# PSPS_AVNC_SRD_central-2020-11-2_FABRICAT.net
KiCad netlist of a schematic drawn in EAGLE
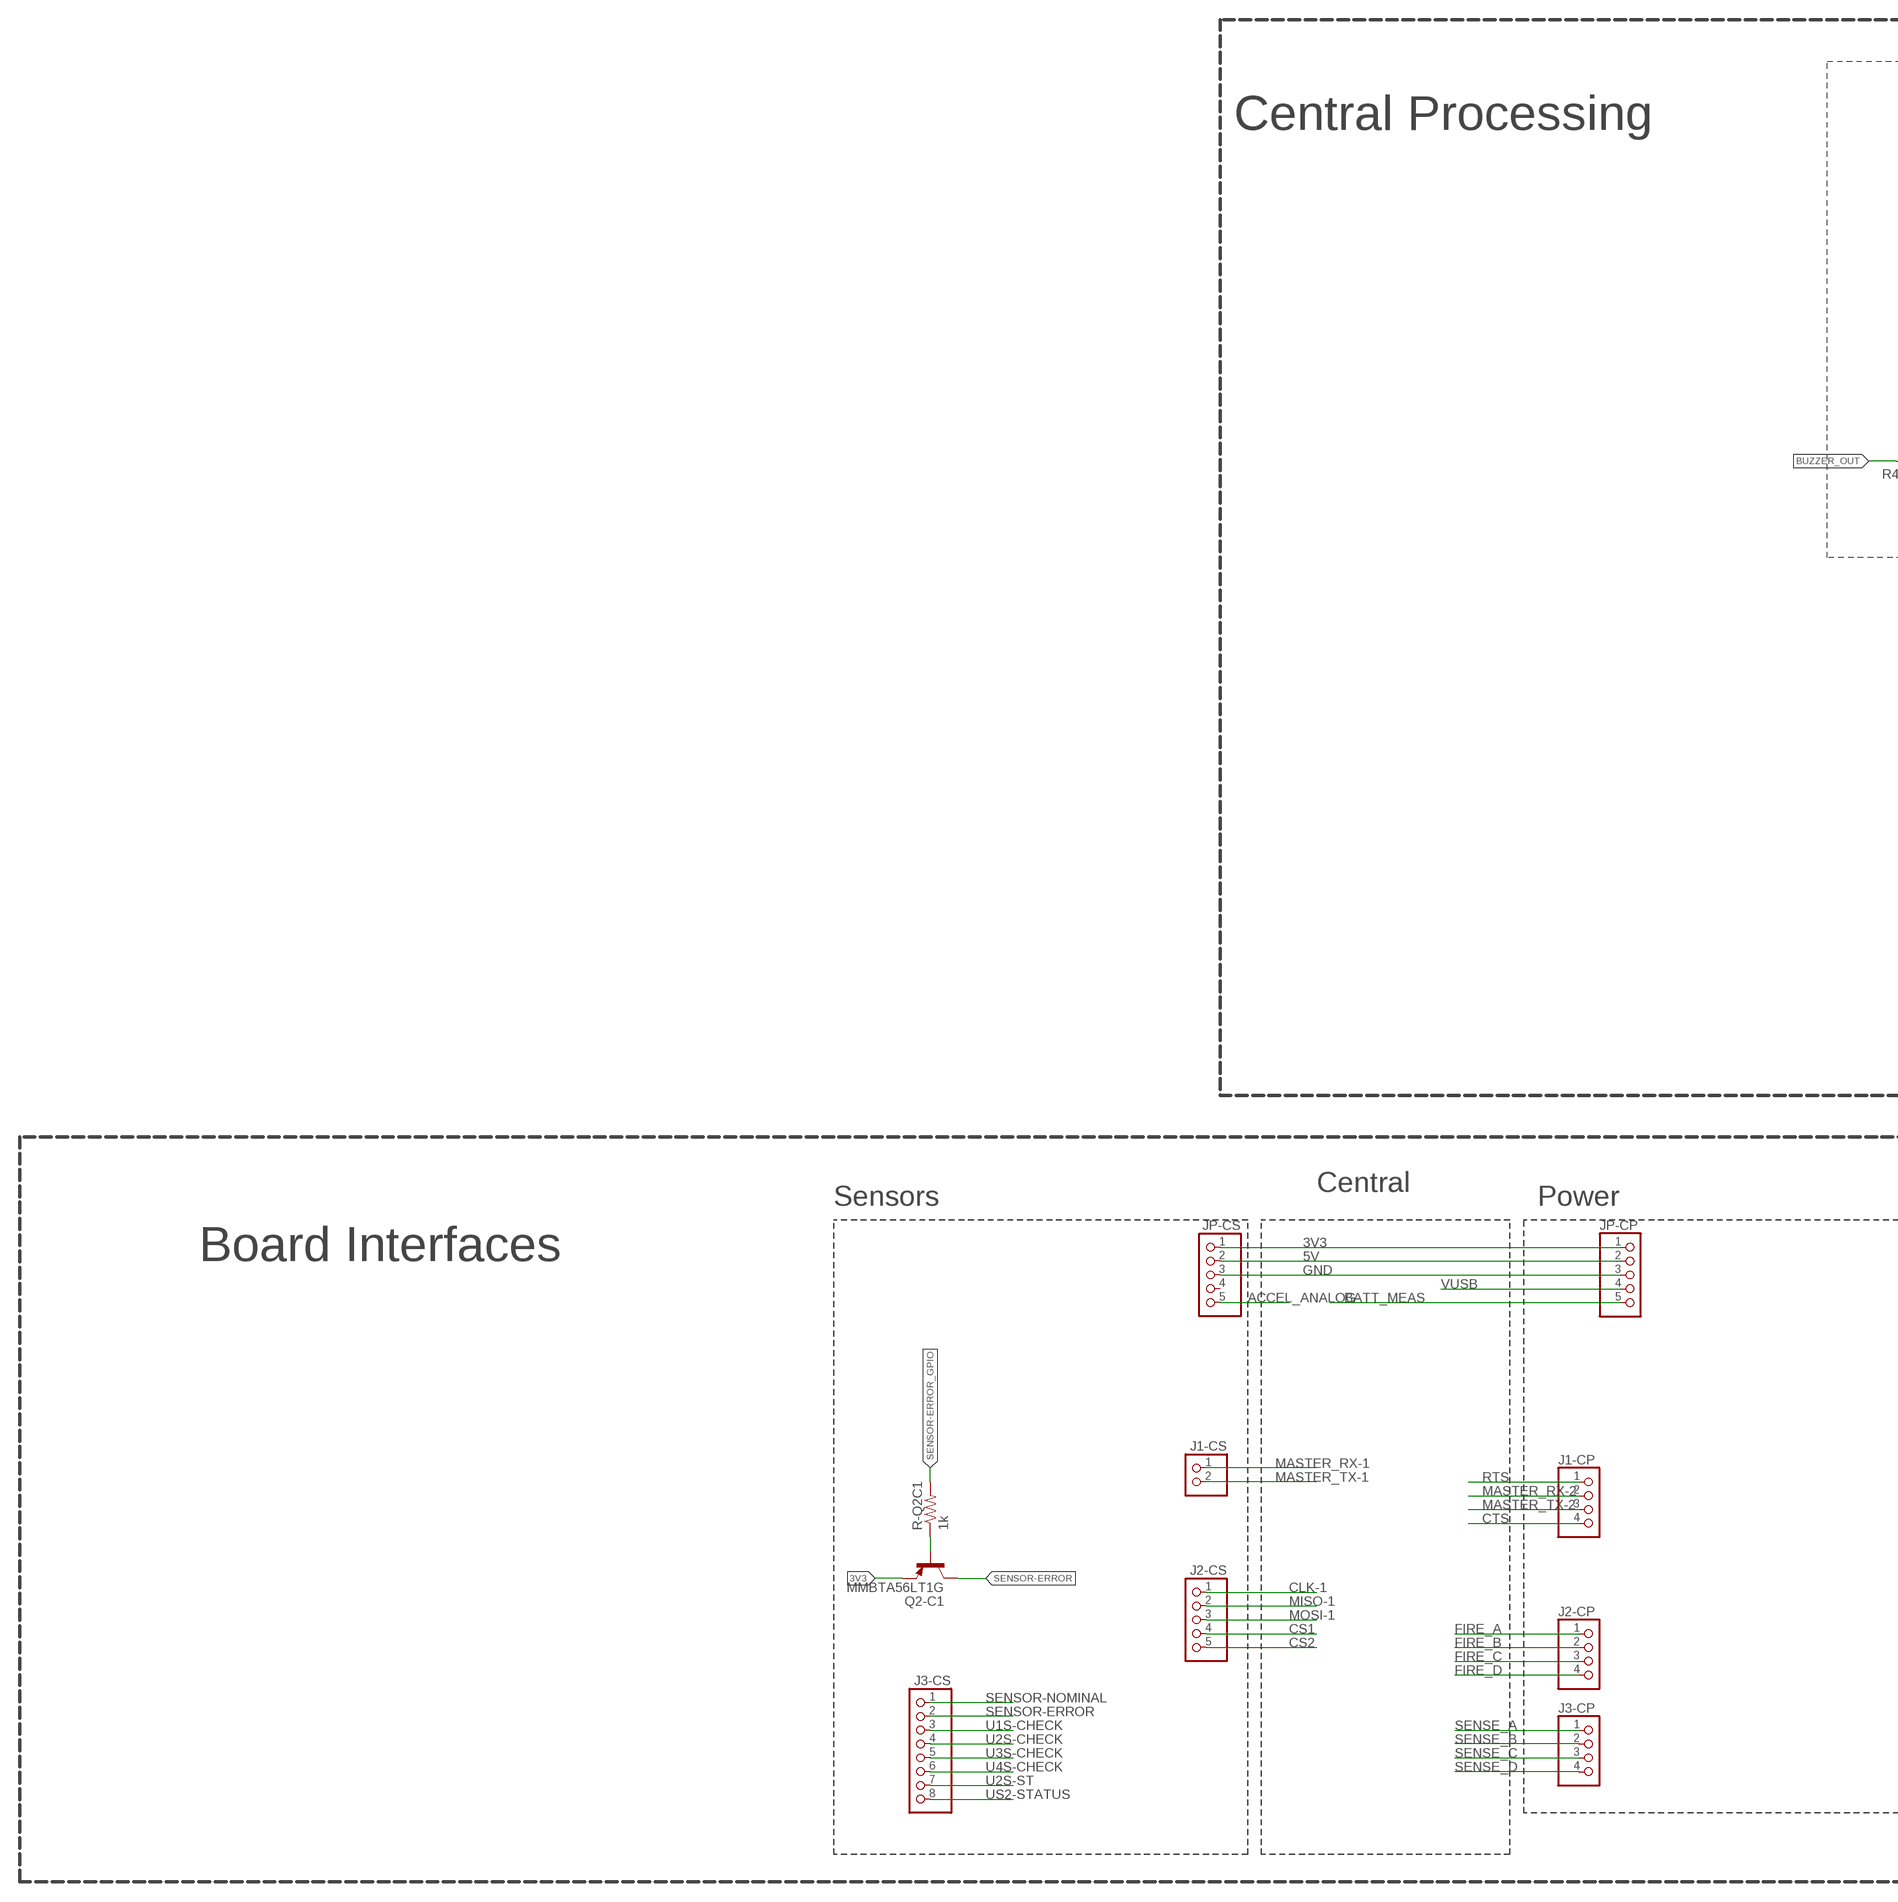
[diagram p0: schematic, sheet 1, part 1 of 2]
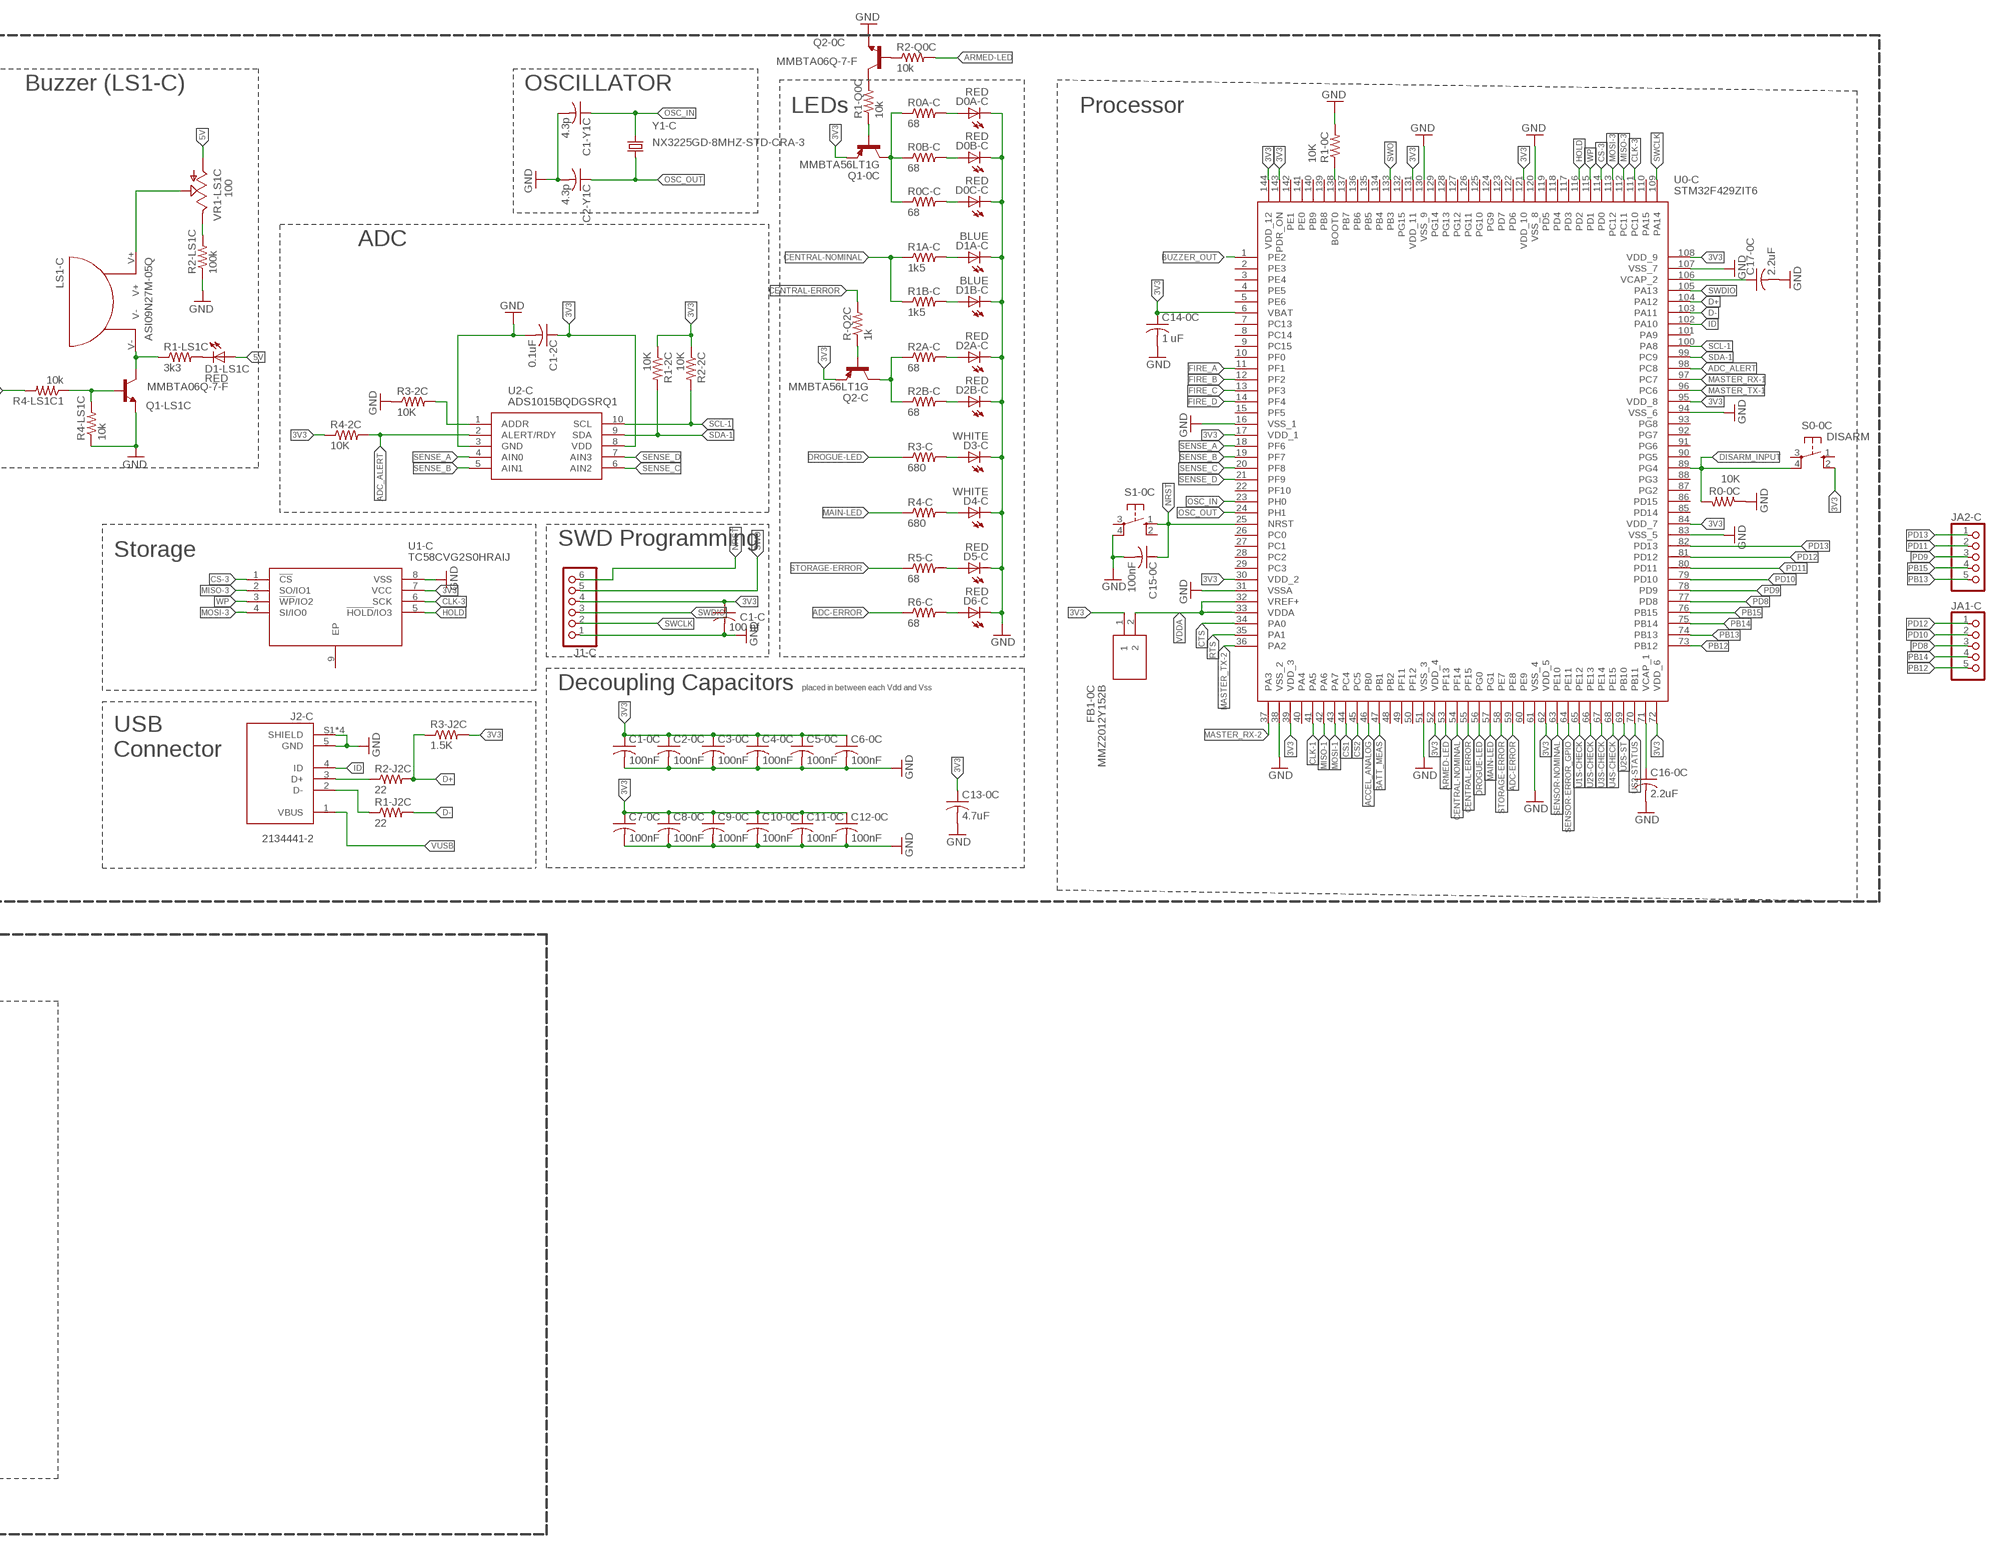
[diagram p1: schematic, sheet 1, part 2 of 2]

(export (version "E")
  (design (tool "Eeschema 10.0.6"))
  (components
    (comp (ref "C1-0C")
      (value "100nF")
      (footprint "eagle-import:C0805")
      (libsource (lib "eagle-import") (part "C-USC0805"))
    )
    (comp (ref "C1-2C")
      (value "0.1uF")
      (footprint "eagle-import:C0805")
      (libsource (lib "eagle-import") (part "C-USC0805"))
    )
    (comp (ref "C1-C")
      (value "100 nf")
      (footprint "eagle-import:C0805")
      (libsource (lib "eagle-import") (part "C-USC0805"))
    )
    (comp (ref "C1-Y1C")
      (value "4.3p")
      (footprint "eagle-import:C0805")
      (libsource (lib "eagle-import") (part "C-USC0805"))
    )
    (comp (ref "C2-0C")
      (value "100nF")
      (footprint "eagle-import:C0805")
      (libsource (lib "eagle-import") (part "C-USC0805"))
    )
    (comp (ref "C2-Y1C")
      (value "4.3p")
      (footprint "eagle-import:C0805")
      (libsource (lib "eagle-import") (part "C-USC0805"))
    )
    (comp (ref "C3-0C")
      (value "100nF")
      (footprint "eagle-import:C0805")
      (libsource (lib "eagle-import") (part "C-USC0805"))
    )
    (comp (ref "C4-0C")
      (value "100nF")
      (footprint "eagle-import:C0805")
      (libsource (lib "eagle-import") (part "C-USC0805"))
    )
    (comp (ref "C5-0C")
      (value "100nF")
      (footprint "eagle-import:C0805")
      (libsource (lib "eagle-import") (part "C-USC0805"))
    )
    (comp (ref "C6-0C")
      (value "100nF")
      (footprint "eagle-import:C0805")
      (libsource (lib "eagle-import") (part "C-USC0805"))
    )
    (comp (ref "C7-0C")
      (value "100nF")
      (footprint "eagle-import:C0805")
      (libsource (lib "eagle-import") (part "C-USC0805"))
    )
    (comp (ref "C8-0C")
      (value "100nF")
      (footprint "eagle-import:C0805")
      (libsource (lib "eagle-import") (part "C-USC0805"))
    )
    (comp (ref "C9-0C")
      (value "100nF")
      (footprint "eagle-import:C0805")
      (libsource (lib "eagle-import") (part "C-USC0805"))
    )
    (comp (ref "C10-0C")
      (value "100nF")
      (footprint "eagle-import:C0805")
      (libsource (lib "eagle-import") (part "C-USC0805"))
    )
    (comp (ref "C11-0C")
      (value "100nF")
      (footprint "eagle-import:C0805")
      (libsource (lib "eagle-import") (part "C-USC0805"))
    )
    (comp (ref "C12-0C")
      (value "100nF")
      (footprint "eagle-import:C0805")
      (libsource (lib "eagle-import") (part "C-USC0805"))
    )
    (comp (ref "C13-0C")
      (value "4.7uF")
      (footprint "eagle-import:C0805")
      (libsource (lib "eagle-import") (part "C-USC0805"))
    )
    (comp (ref "C14-0C")
      (value "1 uF")
      (footprint "eagle-import:C0805")
      (libsource (lib "eagle-import") (part "C-USC0805"))
    )
    (comp (ref "C15-0C")
      (value "100nF")
      (footprint "eagle-import:C0805")
      (libsource (lib "eagle-import") (part "C-USC0805"))
    )
    (comp (ref "C16-0C")
      (value "2.2uF")
      (footprint "eagle-import:C0805")
      (libsource (lib "eagle-import") (part "C-USC0805"))
    )
    (comp (ref "C17-0C")
      (value "2.2uF")
      (footprint "eagle-import:C0805")
      (libsource (lib "eagle-import") (part "C-USC0805"))
    )
    (comp (ref "D0A-C")
      (value "RED")
      (footprint "eagle-import:CHIPLED_0805")
      (libsource (lib "eagle-import") (part "LEDCHIPLED_0805"))
    )
    (comp (ref "D0B-C")
      (value "RED")
      (footprint "eagle-import:CHIPLED_0805")
      (libsource (lib "eagle-import") (part "LEDCHIPLED_0805"))
    )
    (comp (ref "D0C-C")
      (value "RED")
      (footprint "eagle-import:CHIPLED_0805")
      (libsource (lib "eagle-import") (part "LEDCHIPLED_0805"))
    )
    (comp (ref "D1-LS1C")
      (value "RED")
      (footprint "eagle-import:CHIPLED_0805")
      (libsource (lib "eagle-import") (part "LEDCHIPLED_0805"))
    )
    (comp (ref "D1A-C")
      (value "BLUE")
      (footprint "eagle-import:CHIPLED_0805")
      (libsource (lib "eagle-import") (part "LEDCHIPLED_0805"))
    )
    (comp (ref "D1B-C")
      (value "BLUE")
      (footprint "eagle-import:CHIPLED_0805")
      (libsource (lib "eagle-import") (part "LEDCHIPLED_0805"))
    )
    (comp (ref "D2A-C")
      (value "RED")
      (footprint "eagle-import:CHIPLED_0805")
      (libsource (lib "eagle-import") (part "LEDCHIPLED_0805"))
    )
    (comp (ref "D2B-C")
      (value "RED")
      (footprint "eagle-import:CHIPLED_0805")
      (libsource (lib "eagle-import") (part "LEDCHIPLED_0805"))
    )
    (comp (ref "D3-C")
      (value "WHITE")
      (footprint "eagle-import:CHIPLED_0805")
      (libsource (lib "eagle-import") (part "LEDCHIPLED_0805"))
    )
    (comp (ref "D4-C")
      (value "WHITE")
      (footprint "eagle-import:CHIPLED_0805")
      (libsource (lib "eagle-import") (part "LEDCHIPLED_0805"))
    )
    (comp (ref "D5-C")
      (value "RED")
      (footprint "eagle-import:CHIPLED_0805")
      (libsource (lib "eagle-import") (part "LEDCHIPLED_0805"))
    )
    (comp (ref "D6-C")
      (value "RED")
      (footprint "eagle-import:CHIPLED_0805")
      (libsource (lib "eagle-import") (part "LEDCHIPLED_0805"))
    )
    (comp (ref "FB1-0C")
      (value "MMZ2012Y152B")
      (footprint "eagle-import:BEADC2012X105N")
      (fields (field (name "MOUSER_PART_NUMBER") "810-MMZ2012Y152B"))
      (libsource (lib "eagle-import") (part "MMZ2012Y152B"))
    )
    (comp (ref "J1-C")
      (value "PINHD-1X6")
      (footprint "eagle-import:1X06")
      (libsource (lib "eagle-import") (part "PINHD-1X6"))
    )
    (comp (ref "J1-CP")
      (value "PINHD-1X4")
      (footprint "eagle-import:1X04")
      (libsource (lib "eagle-import") (part "PINHD-1X4"))
    )
    (comp (ref "J1-CS")
      (value "PINHD-1X2")
      (footprint "eagle-import:1X02")
      (libsource (lib "eagle-import") (part "PINHD-1X2"))
    )
    (comp (ref "J2-C")
      (value "2134441-2")
      (footprint "eagle-import:TE_2134441-2")
      (fields (field (name "DIGI-KEY_PART_NUMBER") "A118104CT-ND") (field (name "MF") "TE Connectivity"))
      (libsource (lib "eagle-import") (part "2134441-2"))
    )
    (comp (ref "J2-CP")
      (value "PINHD-1X4")
      (footprint "eagle-import:1X04")
      (libsource (lib "eagle-import") (part "PINHD-1X4"))
    )
    (comp (ref "J2-CS")
      (value "PINHD-1X5")
      (footprint "eagle-import:1X05")
      (libsource (lib "eagle-import") (part "PINHD-1X5"))
    )
    (comp (ref "J3-CP")
      (value "PINHD-1X4")
      (footprint "eagle-import:1X04")
      (libsource (lib "eagle-import") (part "PINHD-1X4"))
    )
    (comp (ref "J3-CS")
      (value "PINHD-1X8")
      (footprint "eagle-import:1X08")
      (libsource (lib "eagle-import") (part "PINHD-1X8"))
    )
    (comp (ref "JA1-C")
      (value "PINHD-1X5")
      (footprint "eagle-import:1X05")
      (libsource (lib "eagle-import") (part "PINHD-1X5"))
    )
    (comp (ref "JA2-C")
      (value "PINHD-1X5")
      (footprint "eagle-import:1X05")
      (libsource (lib "eagle-import") (part "PINHD-1X5"))
    )
    (comp (ref "JP-CP")
      (value "PINHD-1X5")
      (footprint "eagle-import:1X05")
      (libsource (lib "eagle-import") (part "PINHD-1X5"))
    )
    (comp (ref "JP-CS")
      (value "PINHD-1X5")
      (footprint "eagle-import:1X05")
      (libsource (lib "eagle-import") (part "PINHD-1X5"))
    )
    (comp (ref "LS1-C")
      (value "ASI09N27M-05Q")
      (footprint "eagle-import:ASI09N27M-05Q")
      (libsource (lib "eagle-import") (part "ASI09N27M-05Q"))
    )
    (comp (ref "Q1-0C")
      (value "MMBTA56LT1G")
      (footprint "eagle-import:SOT23")
      (libsource (lib "eagle-import") (part "PNP_TRANSISTOR"))
    )
    (comp (ref "Q1-LS1C")
      (value "MMBTA06Q-7-F")
      (footprint "eagle-import:SOT23")
      (libsource (lib "eagle-import") (part "NPN_TRANSISTOR"))
    )
    (comp (ref "Q2-0C")
      (value "MMBTA06Q-7-F")
      (footprint "eagle-import:SOT23")
      (libsource (lib "eagle-import") (part "NPN_TRANSISTOR"))
    )
    (comp (ref "Q2-C")
      (value "MMBTA56LT1G")
      (footprint "eagle-import:SOT23")
      (libsource (lib "eagle-import") (part "PNP_TRANSISTOR"))
    )
    (comp (ref "Q2-C1")
      (value "MMBTA56LT1G")
      (footprint "eagle-import:SOT23")
      (libsource (lib "eagle-import") (part "PNP_TRANSISTOR"))
    )
    (comp (ref "R-Q2C")
      (value "1k")
      (footprint "eagle-import:M0805")
      (libsource (lib "eagle-import") (part "R-US_M0805"))
    )
    (comp (ref "R-Q2C1")
      (value "1k")
      (footprint "eagle-import:M0805")
      (libsource (lib "eagle-import") (part "R-US_M0805"))
    )
    (comp (ref "R0-0C")
      (value "10K")
      (footprint "eagle-import:R0805")
      (libsource (lib "eagle-import") (part "R-US_R0805"))
    )
    (comp (ref "R0A-C")
      (value "68")
      (footprint "eagle-import:M0805")
      (libsource (lib "eagle-import") (part "R-US_M0805"))
    )
    (comp (ref "R0B-C")
      (value "68")
      (footprint "eagle-import:M0805")
      (libsource (lib "eagle-import") (part "R-US_M0805"))
    )
    (comp (ref "R0C-C")
      (value "68")
      (footprint "eagle-import:M0805")
      (libsource (lib "eagle-import") (part "R-US_M0805"))
    )
    (comp (ref "R1-0C")
      (value "10K")
      (footprint "eagle-import:R0805")
      (libsource (lib "eagle-import") (part "R-US_R0805"))
    )
    (comp (ref "R1-2C")
      (value "10K")
      (footprint "eagle-import:R0805")
      (libsource (lib "eagle-import") (part "R-US_R0805"))
    )
    (comp (ref "R1-J2C")
      (value "22")
      (footprint "eagle-import:M0805")
      (libsource (lib "eagle-import") (part "R-US_M0805"))
    )
    (comp (ref "R1-LS1C")
      (value "3k3")
      (footprint "eagle-import:R0805")
      (libsource (lib "eagle-import") (part "resistor_348_R-US_R0805"))
    )
    (comp (ref "R1-Q0C")
      (value "10k")
      (footprint "eagle-import:M0805")
      (libsource (lib "eagle-import") (part "R-US_M0805"))
    )
    (comp (ref "R1A-C")
      (value "1k5")
      (footprint "eagle-import:M0805")
      (libsource (lib "eagle-import") (part "R-US_M0805"))
    )
    (comp (ref "R1B-C")
      (value "1k5")
      (footprint "eagle-import:M0805")
      (libsource (lib "eagle-import") (part "R-US_M0805"))
    )
    (comp (ref "R2-2C")
      (value "10K")
      (footprint "eagle-import:R0805")
      (libsource (lib "eagle-import") (part "R-US_R0805"))
    )
    (comp (ref "R2-J2C")
      (value "22")
      (footprint "eagle-import:M0805")
      (libsource (lib "eagle-import") (part "R-US_M0805"))
    )
    (comp (ref "R2-LS1C")
      (value "100k")
      (footprint "eagle-import:R0805")
      (libsource (lib "eagle-import") (part "resistor_348_R-US_R0805"))
    )
    (comp (ref "R2-Q0C")
      (value "10k")
      (footprint "eagle-import:M0805")
      (libsource (lib "eagle-import") (part "R-US_M0805"))
    )
    (comp (ref "R2A-C")
      (value "68")
      (footprint "eagle-import:M0805")
      (libsource (lib "eagle-import") (part "R-US_M0805"))
    )
    (comp (ref "R2B-C")
      (value "68")
      (footprint "eagle-import:M0805")
      (libsource (lib "eagle-import") (part "R-US_M0805"))
    )
    (comp (ref "R3-2C")
      (value "10K")
      (footprint "eagle-import:R0805")
      (libsource (lib "eagle-import") (part "R-US_R0805"))
    )
    (comp (ref "R3-C")
      (value "680")
      (footprint "eagle-import:M0805")
      (libsource (lib "eagle-import") (part "R-US_M0805"))
    )
    (comp (ref "R3-J2C")
      (value "1.5K")
      (footprint "eagle-import:M0805")
      (libsource (lib "eagle-import") (part "R-US_M0805"))
    )
    (comp (ref "R4-2C")
      (value "10K")
      (footprint "eagle-import:R0805")
      (libsource (lib "eagle-import") (part "R-US_R0805"))
    )
    (comp (ref "R4-C")
      (value "680")
      (footprint "eagle-import:M0805")
      (libsource (lib "eagle-import") (part "R-US_M0805"))
    )
    (comp (ref "R4-LS1C")
      (value "10k")
      (footprint "eagle-import:R0805")
      (libsource (lib "eagle-import") (part "resistor_348_R-US_R0805"))
    )
    (comp (ref "R4-LS1C1")
      (value "10k")
      (footprint "eagle-import:R0805")
      (libsource (lib "eagle-import") (part "resistor_348_R-US_R0805"))
    )
    (comp (ref "R5-C")
      (value "68")
      (footprint "eagle-import:M0805")
      (libsource (lib "eagle-import") (part "R-US_M0805"))
    )
    (comp (ref "R6-C")
      (value "68")
      (footprint "eagle-import:M0805")
      (libsource (lib "eagle-import") (part "R-US_M0805"))
    )
    (comp (ref "S0-0C")
      (value "DISARM")
      (footprint "eagle-import:B3F-10XX")
      (fields (field (name "MPN") "B3F-1000"))
      (libsource (lib "eagle-import") (part "10-XX"))
    )
    (comp (ref "S1-0C")
      (value "10-XX")
      (footprint "eagle-import:B3F-10XX")
      (fields (field (name "MPN") "B3F-1000"))
      (libsource (lib "eagle-import") (part "10-XX"))
    )
    (comp (ref "U0-C")
      (value "STM32F429ZIT6")
      (footprint "eagle-import:QFP50P2200X2200X160-144N")
      (fields (field (name "MOUSER_PART_NUMBER") "511-STM32F429ZIT6"))
      (libsource (lib "eagle-import") (part "STM32F429ZIT6"))
    )
    (comp (ref "U1-C")
      (value "TC58CVG2S0HRAIJ")
      (footprint "eagle-import:SON127P800X600X80-9N")
      (fields (field (name "MOUSER_PART_NUMBER") "757-TC58CVG2S0HRAIJ"))
      (libsource (lib "eagle-import") (part "TC58CVG2S0HRAIJ"))
    )
    (comp (ref "U2-C")
      (value "ADS1015BQDGSRQ1")
      (footprint "eagle-import:SOP50P490X110-10N")
      (fields (field (name "MOUSER_PART_NUMBER") "595-ADS1015BQDGSRQ1"))
      (libsource (lib "eagle-import") (part "ADS1015BQDGSRQ1"))
    )
    (comp (ref "VR1-LS1C")
      (value "100")
      (footprint "eagle-import:LI10")
      (libsource (lib "eagle-import") (part "TRIM_US-LI10"))
    )
    (comp (ref "Y1-C")
      (value "NX3225GD-8MHZ-STD-CRA-3")
      (footprint "eagle-import:NX3225GD")
      (libsource (lib "eagle-import") (part "NX3225GD"))
    )
  )
  (nets
    (net (code "1") (name "3V3") (class "Default")
      (node (ref "C1-0C") (pin "1") (pinfunction "1_1") (pintype "passive"))
      (node (ref "C1-2C") (pin "1") (pinfunction "1_1") (pintype "passive"))
      (node (ref "C1-C") (pin "1") (pinfunction "1_1") (pintype "passive"))
      (node (ref "C10-0C") (pin "1") (pinfunction "1_1") (pintype "passive"))
      (node (ref "C11-0C") (pin "1") (pinfunction "1_1") (pintype "passive"))
      (node (ref "C12-0C") (pin "1") (pinfunction "1_1") (pintype "passive"))
      (node (ref "C13-0C") (pin "1") (pinfunction "1_1") (pintype "passive"))
      (node (ref "C14-0C") (pin "1") (pinfunction "1_1") (pintype "passive"))
      (node (ref "C2-0C") (pin "1") (pinfunction "1_1") (pintype "passive"))
      (node (ref "C3-0C") (pin "1") (pinfunction "1_1") (pintype "passive"))
      (node (ref "C4-0C") (pin "1") (pinfunction "1_1") (pintype "passive"))
      (node (ref "C5-0C") (pin "1") (pinfunction "1_1") (pintype "passive"))
      (node (ref "C6-0C") (pin "1") (pinfunction "1_1") (pintype "passive"))
      (node (ref "C7-0C") (pin "1") (pinfunction "1_1") (pintype "passive"))
      (node (ref "C8-0C") (pin "1") (pinfunction "1_1") (pintype "passive"))
      (node (ref "C9-0C") (pin "1") (pinfunction "1_1") (pintype "passive"))
      (node (ref "FB1-0C") (pin "1") (pinfunction "1_1") (pintype "bidirectional"))
      (node (ref "J1-C") (pin "4") (pinfunction "4_4") (pintype "passive"))
      (node (ref "JP-CP") (pin "1") (pinfunction "1_1") (pintype "passive"))
      (node (ref "JP-CS") (pin "1") (pinfunction "1_1") (pintype "passive"))
      (node (ref "Q1-0C") (pin "2") (pinfunction "E_2") (pintype "passive"))
      (node (ref "Q2-C") (pin "2") (pinfunction "E_2") (pintype "passive"))
      (node (ref "Q2-C1") (pin "2") (pinfunction "E_2") (pintype "passive"))
      (node (ref "R1-2C") (pin "1") (pinfunction "1_1") (pintype "passive"))
      (node (ref "R2-2C") (pin "1") (pinfunction "1_1") (pintype "passive"))
      (node (ref "R3-J2C") (pin "2") (pinfunction "2_2") (pintype "passive"))
      (node (ref "R4-2C") (pin "1") (pinfunction "1_1") (pintype "passive"))
      (node (ref "S0-0C") (pin "2") (pinfunction "S1_2") (pintype "passive"))
      (node (ref "U0-C") (pin "108") (pinfunction "VDD_9_108") (pintype "power_in"))
      (node (ref "U0-C") (pin "121") (pinfunction "VDD_10_121") (pintype "power_in"))
      (node (ref "U0-C") (pin "131") (pinfunction "VDD_11_131") (pintype "power_in"))
      (node (ref "U0-C") (pin "143") (pinfunction "PDR_ON_143") (pintype "bidirectional"))
      (node (ref "U0-C") (pin "144") (pinfunction "VDD_12_144") (pintype "power_in"))
      (node (ref "U0-C") (pin "17") (pinfunction "VDD_1_17") (pintype "power_in"))
      (node (ref "U0-C") (pin "30") (pinfunction "VDD_2_30") (pintype "power_in"))
      (node (ref "U0-C") (pin "39") (pinfunction "VDD_3_39") (pintype "power_in"))
      (node (ref "U0-C") (pin "52") (pinfunction "VDD_4_52") (pintype "power_in"))
      (node (ref "U0-C") (pin "6") (pinfunction "VBAT_6") (pintype "bidirectional"))
      (node (ref "U0-C") (pin "62") (pinfunction "VDD_5_62") (pintype "power_in"))
      (node (ref "U0-C") (pin "72") (pinfunction "VDD_6_72") (pintype "power_in"))
      (node (ref "U0-C") (pin "84") (pinfunction "VDD_7_84") (pintype "power_in"))
      (node (ref "U0-C") (pin "95") (pinfunction "VDD_8_95") (pintype "power_in"))
      (node (ref "U1-C") (pin "7") (pinfunction "VCC_7") (pintype "bidirectional"))
      (node (ref "U2-C") (pin "8") (pinfunction "VDD_8") (pintype "bidirectional"))
    )
    (net (code "2") (name "5V") (class "Default")
      (node (ref "D1-LS1C") (pin "A") (pinfunction "A_A") (pintype "passive"))
      (node (ref "JP-CP") (pin "2") (pinfunction "2_2") (pintype "passive"))
      (node (ref "JP-CS") (pin "2") (pinfunction "2_2") (pintype "passive"))
      (node (ref "VR1-LS1C") (pin "A") (pinfunction "A_A") (pintype "passive"))
    )
    (net (code "3") (name "ACCEL_ANALOG") (class "Default")
      (node (ref "JP-CS") (pin "5") (pinfunction "5_5") (pintype "passive"))
      (node (ref "U0-C") (pin "46") (pinfunction "PB0_46") (pintype "bidirectional"))
    )
    (net (code "4") (name "ADC-ERROR") (class "Default")
      (node (ref "R6-C") (pin "1") (pinfunction "1_1") (pintype "passive"))
      (node (ref "U0-C") (pin "59") (pinfunction "PE8_59") (pintype "bidirectional"))
    )
    (net (code "5") (name "ADC_ALERT") (class "Default")
      (node (ref "R4-2C") (pin "2") (pinfunction "2_2") (pintype "passive"))
      (node (ref "U0-C") (pin "98") (pinfunction "PC8_98") (pintype "bidirectional"))
      (node (ref "U2-C") (pin "2") (pinfunction "ALERT/RDY_2") (pintype "bidirectional"))
    )
    (net (code "6") (name "ARMED-LED") (class "Default")
      (node (ref "R2-Q0C") (pin "2") (pinfunction "2_2") (pintype "passive"))
      (node (ref "U0-C") (pin "53") (pinfunction "PF13_53") (pintype "bidirectional"))
    )
    (net (code "7") (name "BATT_MEAS") (class "Default")
      (node (ref "JP-CP") (pin "5") (pinfunction "5_5") (pintype "passive"))
      (node (ref "U0-C") (pin "47") (pinfunction "PB1_47") (pintype "bidirectional"))
    )
    (net (code "8") (name "BUZZER_OUT") (class "Default")
      (node (ref "R4-LS1C1") (pin "2") (pinfunction "2_2") (pintype "passive"))
      (node (ref "U0-C") (pin "1") (pinfunction "PE2_1") (pintype "bidirectional"))
    )
    (net (code "9") (name "CENTRAL-ERROR") (class "Default")
      (node (ref "R-Q2C") (pin "2") (pinfunction "2_2") (pintype "passive"))
      (node (ref "U0-C") (pin "55") (pinfunction "PF15_55") (pintype "bidirectional"))
    )
    (net (code "10") (name "CENTRAL-NOMINAL") (class "Default")
      (node (ref "R1A-C") (pin "1") (pinfunction "1_1") (pintype "passive"))
      (node (ref "R1B-C") (pin "1") (pinfunction "1_1") (pintype "passive"))
      (node (ref "U0-C") (pin "54") (pinfunction "PF14_54") (pintype "bidirectional"))
    )
    (net (code "11") (name "CLK-1") (class "Default")
      (node (ref "J2-CS") (pin "1") (pinfunction "1_1") (pintype "passive"))
      (node (ref "U0-C") (pin "41") (pinfunction "PA5_41") (pintype "bidirectional"))
    )
    (net (code "12") (name "CLK-3") (class "Default")
      (node (ref "U0-C") (pin "111") (pinfunction "PC10_111") (pintype "bidirectional"))
      (node (ref "U1-C") (pin "6") (pinfunction "SCK_6") (pintype "bidirectional"))
    )
    (net (code "13") (name "CS-3") (class "Default")
      (node (ref "U0-C") (pin "114") (pinfunction "PD0_114") (pintype "bidirectional"))
      (node (ref "U1-C") (pin "1") (pinfunction "~{CS}_1") (pintype "bidirectional"))
    )
    (net (code "14") (name "CS1") (class "Default")
      (node (ref "J2-CS") (pin "4") (pinfunction "4_4") (pintype "passive"))
      (node (ref "U0-C") (pin "44") (pinfunction "PC4_44") (pintype "bidirectional"))
    )
    (net (code "15") (name "CS2") (class "Default")
      (node (ref "J2-CS") (pin "5") (pinfunction "5_5") (pintype "passive"))
      (node (ref "U0-C") (pin "45") (pinfunction "PC5_45") (pintype "bidirectional"))
    )
    (net (code "16") (name "CTS") (class "Default")
      (node (ref "J1-CP") (pin "4") (pinfunction "4_4") (pintype "passive"))
      (node (ref "U0-C") (pin "34") (pinfunction "PA0_34") (pintype "bidirectional"))
    )
    (net (code "17") (name "D+") (class "Default")
      (node (ref "R2-J2C") (pin "2") (pinfunction "2_2") (pintype "passive"))
      (node (ref "R3-J2C") (pin "1") (pinfunction "1_1") (pintype "passive"))
      (node (ref "U0-C") (pin "104") (pinfunction "PA12_104") (pintype "bidirectional"))
    )
    (net (code "18") (name "D-") (class "Default")
      (node (ref "R1-J2C") (pin "2") (pinfunction "2_2") (pintype "passive"))
      (node (ref "U0-C") (pin "103") (pinfunction "PA11_103") (pintype "bidirectional"))
    )
    (net (code "19") (name "DISARM_INPUT") (class "Default")
      (node (ref "R0-0C") (pin "2") (pinfunction "2_2") (pintype "passive"))
      (node (ref "S0-0C") (pin "4") (pinfunction "P1_4") (pintype "passive"))
      (node (ref "U0-C") (pin "89") (pinfunction "PG4_89") (pintype "bidirectional"))
    )
    (net (code "20") (name "DROGUE-LED") (class "Default")
      (node (ref "R3-C") (pin "1") (pinfunction "1_1") (pintype "passive"))
      (node (ref "U0-C") (pin "56") (pinfunction "PG0_56") (pintype "bidirectional"))
    )
    (net (code "21") (name "FIRE_A") (class "Default")
      (node (ref "J2-CP") (pin "1") (pinfunction "1_1") (pintype "passive"))
      (node (ref "U0-C") (pin "11") (pinfunction "PF1_11") (pintype "bidirectional"))
    )
    (net (code "22") (name "FIRE_B") (class "Default")
      (node (ref "J2-CP") (pin "2") (pinfunction "2_2") (pintype "passive"))
      (node (ref "U0-C") (pin "12") (pinfunction "PF2_12") (pintype "bidirectional"))
    )
    (net (code "23") (name "FIRE_C") (class "Default")
      (node (ref "J2-CP") (pin "3") (pinfunction "3_3") (pintype "passive"))
      (node (ref "U0-C") (pin "13") (pinfunction "PF3_13") (pintype "bidirectional"))
    )
    (net (code "24") (name "FIRE_D") (class "Default")
      (node (ref "J2-CP") (pin "4") (pinfunction "4_4") (pintype "passive"))
      (node (ref "U0-C") (pin "14") (pinfunction "PF4_14") (pintype "bidirectional"))
    )
    (net (code "25") (name "GND") (class "Default")
      (node (ref "C1-0C") (pin "2") (pinfunction "2_2") (pintype "passive"))
      (node (ref "C1-2C") (pin "2") (pinfunction "2_2") (pintype "passive"))
      (node (ref "C1-C") (pin "2") (pinfunction "2_2") (pintype "passive"))
      (node (ref "C1-Y1C") (pin "2") (pinfunction "2_2") (pintype "passive"))
      (node (ref "C10-0C") (pin "2") (pinfunction "2_2") (pintype "passive"))
      (node (ref "C11-0C") (pin "2") (pinfunction "2_2") (pintype "passive"))
      (node (ref "C12-0C") (pin "2") (pinfunction "2_2") (pintype "passive"))
      (node (ref "C13-0C") (pin "2") (pinfunction "2_2") (pintype "passive"))
      (node (ref "C14-0C") (pin "2") (pinfunction "2_2") (pintype "passive"))
      (node (ref "C15-0C") (pin "2") (pinfunction "2_2") (pintype "passive"))
      (node (ref "C16-0C") (pin "2") (pinfunction "2_2") (pintype "passive"))
      (node (ref "C17-0C") (pin "2") (pinfunction "2_2") (pintype "passive"))
      (node (ref "C2-0C") (pin "2") (pinfunction "2_2") (pintype "passive"))
      (node (ref "C2-Y1C") (pin "2") (pinfunction "2_2") (pintype "passive"))
      (node (ref "C3-0C") (pin "2") (pinfunction "2_2") (pintype "passive"))
      (node (ref "C4-0C") (pin "2") (pinfunction "2_2") (pintype "passive"))
      (node (ref "C5-0C") (pin "2") (pinfunction "2_2") (pintype "passive"))
      (node (ref "C6-0C") (pin "2") (pinfunction "2_2") (pintype "passive"))
      (node (ref "C7-0C") (pin "2") (pinfunction "2_2") (pintype "passive"))
      (node (ref "C8-0C") (pin "2") (pinfunction "2_2") (pintype "passive"))
      (node (ref "C9-0C") (pin "2") (pinfunction "2_2") (pintype "passive"))
      (node (ref "D0A-C") (pin "C") (pinfunction "C_C") (pintype "passive"))
      (node (ref "D0B-C") (pin "C") (pinfunction "C_C") (pintype "passive"))
      (node (ref "D0C-C") (pin "C") (pinfunction "C_C") (pintype "passive"))
      (node (ref "D1A-C") (pin "C") (pinfunction "C_C") (pintype "passive"))
      (node (ref "D1B-C") (pin "C") (pinfunction "C_C") (pintype "passive"))
      (node (ref "D2A-C") (pin "C") (pinfunction "C_C") (pintype "passive"))
      (node (ref "D2B-C") (pin "C") (pinfunction "C_C") (pintype "passive"))
      (node (ref "D3-C") (pin "C") (pinfunction "C_C") (pintype "passive"))
      (node (ref "D4-C") (pin "C") (pinfunction "C_C") (pintype "passive"))
      (node (ref "D5-C") (pin "C") (pinfunction "C_C") (pintype "passive"))
      (node (ref "D6-C") (pin "C") (pinfunction "C_C") (pintype "passive"))
      (node (ref "J1-C") (pin "1") (pinfunction "1_1") (pintype "passive"))
      (node (ref "J2-C") (pin "5") (pinfunction "GND_5") (pintype "power_in"))
      (node (ref "J2-C") (pin "S1") (pinfunction "SHIELD_S1") (pintype "power_in"))
      (node (ref "J2-C") (pin "S2") (pinfunction "SHIELD_S2") (pintype "power_in"))
      (node (ref "J2-C") (pin "S3") (pinfunction "SHIELD_S3") (pintype "power_in"))
      (node (ref "J2-C") (pin "S4") (pinfunction "SHIELD_S4") (pintype "power_in"))
      (node (ref "JP-CP") (pin "3") (pinfunction "3_3") (pintype "passive"))
      (node (ref "JP-CS") (pin "3") (pinfunction "3_3") (pintype "passive"))
      (node (ref "Q1-LS1C") (pin "3") (pinfunction "E_3") (pintype "passive"))
      (node (ref "Q2-0C") (pin "3") (pinfunction "E_3") (pintype "passive"))
      (node (ref "R0-0C") (pin "1") (pinfunction "1_1") (pintype "passive"))
      (node (ref "R1-0C") (pin "2") (pinfunction "2_2") (pintype "passive"))
      (node (ref "R2-LS1C") (pin "1") (pinfunction "1_1") (pintype "passive"))
      (node (ref "R3-2C") (pin "1") (pinfunction "1_1") (pintype "passive"))
      (node (ref "R4-LS1C") (pin "1") (pinfunction "1_1") (pintype "passive"))
      (node (ref "S1-0C") (pin "4") (pinfunction "P1_4") (pintype "passive"))
      (node (ref "U0-C") (pin "107") (pinfunction "VSS_7_107") (pintype "power_in"))
      (node (ref "U0-C") (pin "120") (pinfunction "VSS_8_120") (pintype "power_in"))
      (node (ref "U0-C") (pin "130") (pinfunction "VSS_9_130") (pintype "power_in"))
      (node (ref "U0-C") (pin "16") (pinfunction "VSS_1_16") (pintype "power_in"))
      (node (ref "U0-C") (pin "31") (pinfunction "VSSA_31") (pintype "power_in"))
      (node (ref "U0-C") (pin "38") (pinfunction "VSS_2_38") (pintype "power_in"))
      (node (ref "U0-C") (pin "51") (pinfunction "VSS_3_51") (pintype "power_in"))
      (node (ref "U0-C") (pin "61") (pinfunction "VSS_4_61") (pintype "power_in"))
      (node (ref "U0-C") (pin "83") (pinfunction "VSS_5_83") (pintype "power_in"))
      (node (ref "U0-C") (pin "94") (pinfunction "VSS_6_94") (pintype "power_in"))
      (node (ref "U1-C") (pin "8") (pinfunction "VSS_8") (pintype "bidirectional"))
      (node (ref "U2-C") (pin "3") (pinfunction "GND_3") (pintype "bidirectional"))
    )
    (net (code "26") (name "HOLD") (class "Default")
      (node (ref "U0-C") (pin "116") (pinfunction "PD2_116") (pintype "bidirectional"))
      (node (ref "U1-C") (pin "5") (pinfunction "~{HOLD}/IO3_5") (pintype "bidirectional"))
    )
    (net (code "27") (name "ID") (class "Default")
      (node (ref "J2-C") (pin "4") (pinfunction "ID_4") (pintype "bidirectional"))
      (node (ref "U0-C") (pin "102") (pinfunction "PA10_102") (pintype "bidirectional"))
    )
    (net (code "28") (name "MAIN-LED") (class "Default")
      (node (ref "R4-C") (pin "1") (pinfunction "1_1") (pintype "passive"))
      (node (ref "U0-C") (pin "57") (pinfunction "PG1_57") (pintype "bidirectional"))
    )
    (net (code "29") (name "MASTER_RX-1") (class "Default")
      (node (ref "J1-CS") (pin "1") (pinfunction "1_1") (pintype "passive"))
      (node (ref "U0-C") (pin "97") (pinfunction "PC7_97") (pintype "bidirectional"))
    )
    (net (code "30") (name "MASTER_RX-2") (class "Default")
      (node (ref "J1-CP") (pin "2") (pinfunction "2_2") (pintype "passive"))
      (node (ref "U0-C") (pin "37") (pinfunction "PA3_37") (pintype "bidirectional"))
    )
    (net (code "31") (name "MASTER_TX-1") (class "Default")
      (node (ref "J1-CS") (pin "2") (pinfunction "2_2") (pintype "passive"))
      (node (ref "U0-C") (pin "96") (pinfunction "PC6_96") (pintype "bidirectional"))
    )
    (net (code "32") (name "MASTER_TX-2") (class "Default")
      (node (ref "J1-CP") (pin "3") (pinfunction "3_3") (pintype "passive"))
      (node (ref "U0-C") (pin "36") (pinfunction "PA2_36") (pintype "bidirectional"))
    )
    (net (code "33") (name "MISO-1") (class "Default")
      (node (ref "J2-CS") (pin "2") (pinfunction "2_2") (pintype "passive"))
      (node (ref "U0-C") (pin "42") (pinfunction "PA6_42") (pintype "bidirectional"))
    )
    (net (code "34") (name "MISO-3") (class "Default")
      (node (ref "U0-C") (pin "112") (pinfunction "PC11_112") (pintype "bidirectional"))
      (node (ref "U1-C") (pin "2") (pinfunction "SO/IO1_2") (pintype "bidirectional"))
    )
    (net (code "35") (name "MOSI-1") (class "Default")
      (node (ref "J2-CS") (pin "3") (pinfunction "3_3") (pintype "passive"))
      (node (ref "U0-C") (pin "43") (pinfunction "PA7_43") (pintype "bidirectional"))
    )
    (net (code "36") (name "MOSI-3") (class "Default")
      (node (ref "U0-C") (pin "113") (pinfunction "PC12_113") (pintype "bidirectional"))
      (node (ref "U1-C") (pin "4") (pinfunction "SI/IO0_4") (pintype "bidirectional"))
    )
    (net (code "37") (name "NRST") (class "Default")
      (node (ref "C15-0C") (pin "1") (pinfunction "1_1") (pintype "passive"))
      (node (ref "J1-C") (pin "6") (pinfunction "6_6") (pintype "passive"))
      (node (ref "S1-0C") (pin "1") (pinfunction "S_1") (pintype "passive"))
      (node (ref "U0-C") (pin "25") (pinfunction "NRST_25") (pintype "input"))
    )
    (net (code "38") (name "Net-(D0A-C-PadA)") (class "Default")
      (node (ref "D0A-C") (pin "A") (pinfunction "A_A") (pintype "passive"))
      (node (ref "R0A-C") (pin "2") (pinfunction "2_2") (pintype "passive"))
    )
    (net (code "39") (name "Net-(D0B-C-PadA)") (class "Default")
      (node (ref "D0B-C") (pin "A") (pinfunction "A_A") (pintype "passive"))
      (node (ref "R0B-C") (pin "2") (pinfunction "2_2") (pintype "passive"))
    )
    (net (code "40") (name "Net-(D0C-C-PadA)") (class "Default")
      (node (ref "D0C-C") (pin "A") (pinfunction "A_A") (pintype "passive"))
      (node (ref "R0C-C") (pin "2") (pinfunction "2_2") (pintype "passive"))
    )
    (net (code "41") (name "Net-(D1-LS1C-PadC)") (class "Default")
      (node (ref "D1-LS1C") (pin "C") (pinfunction "C_C") (pintype "passive"))
      (node (ref "R1-LS1C") (pin "2") (pinfunction "2_2") (pintype "passive"))
    )
    (net (code "42") (name "Net-(D1A-C-PadA)") (class "Default")
      (node (ref "D1A-C") (pin "A") (pinfunction "A_A") (pintype "passive"))
      (node (ref "R1A-C") (pin "2") (pinfunction "2_2") (pintype "passive"))
    )
    (net (code "43") (name "Net-(D1B-C-PadA)") (class "Default")
      (node (ref "D1B-C") (pin "A") (pinfunction "A_A") (pintype "passive"))
      (node (ref "R1B-C") (pin "2") (pinfunction "2_2") (pintype "passive"))
    )
    (net (code "44") (name "Net-(D2A-C-PadA)") (class "Default")
      (node (ref "D2A-C") (pin "A") (pinfunction "A_A") (pintype "passive"))
      (node (ref "R2A-C") (pin "2") (pinfunction "2_2") (pintype "passive"))
    )
    (net (code "45") (name "Net-(D2B-C-PadA)") (class "Default")
      (node (ref "D2B-C") (pin "A") (pinfunction "A_A") (pintype "passive"))
      (node (ref "R2B-C") (pin "2") (pinfunction "2_2") (pintype "passive"))
    )
    (net (code "46") (name "Net-(D3-C-PadA)") (class "Default")
      (node (ref "D3-C") (pin "A") (pinfunction "A_A") (pintype "passive"))
      (node (ref "R3-C") (pin "2") (pinfunction "2_2") (pintype "passive"))
    )
    (net (code "47") (name "Net-(D4-C-PadA)") (class "Default")
      (node (ref "D4-C") (pin "A") (pinfunction "A_A") (pintype "passive"))
      (node (ref "R4-C") (pin "2") (pinfunction "2_2") (pintype "passive"))
    )
    (net (code "48") (name "Net-(D5-C-PadA)") (class "Default")
      (node (ref "D5-C") (pin "A") (pinfunction "A_A") (pintype "passive"))
      (node (ref "R5-C") (pin "2") (pinfunction "2_2") (pintype "passive"))
    )
    (net (code "49") (name "Net-(D6-C-PadA)") (class "Default")
      (node (ref "D6-C") (pin "A") (pinfunction "A_A") (pintype "passive"))
      (node (ref "R6-C") (pin "2") (pinfunction "2_2") (pintype "passive"))
    )
    (net (code "50") (name "Net-(J2-C-D+)") (class "Default")
      (node (ref "J2-C") (pin "3") (pinfunction "D+_3") (pintype "bidirectional"))
      (node (ref "R2-J2C") (pin "1") (pinfunction "1_1") (pintype "passive"))
    )
    (net (code "51") (name "Net-(J2-C-D-)") (class "Default")
      (node (ref "J2-C") (pin "2") (pinfunction "D-_2") (pintype "bidirectional"))
      (node (ref "R1-J2C") (pin "1") (pinfunction "1_1") (pintype "passive"))
    )
    (net (code "52") (name "Net-(LS1-C-PadV+)") (class "Default")
      (node (ref "LS1-C") (pin "V+") (pinfunction "V+_V+") (pintype "bidirectional"))
      (node (ref "VR1-LS1C") (pin "S") (pinfunction "S_S") (pintype "passive"))
    )
    (net (code "53") (name "Net-(Q1-0C-B)") (class "Default")
      (node (ref "Q1-0C") (pin "1") (pinfunction "B_1") (pintype "passive"))
      (node (ref "R1-Q0C") (pin "1") (pinfunction "1_1") (pintype "passive"))
    )
    (net (code "54") (name "Net-(Q1-0C-C)") (class "Default")
      (node (ref "Q1-0C") (pin "3") (pinfunction "C_3") (pintype "passive"))
      (node (ref "R0A-C") (pin "1") (pinfunction "1_1") (pintype "passive"))
      (node (ref "R0B-C") (pin "1") (pinfunction "1_1") (pintype "passive"))
      (node (ref "R0C-C") (pin "1") (pinfunction "1_1") (pintype "passive"))
    )
    (net (code "55") (name "Net-(Q1-LS1C-B)") (class "Default")
      (node (ref "Q1-LS1C") (pin "1") (pinfunction "B_1") (pintype "passive"))
      (node (ref "R4-LS1C") (pin "2") (pinfunction "2_2") (pintype "passive"))
      (node (ref "R4-LS1C1") (pin "1") (pinfunction "1_1") (pintype "passive"))
    )
    (net (code "56") (name "Net-(Q1-LS1C-C)") (class "Default")
      (node (ref "LS1-C") (pin "V-") (pinfunction "V-_V-") (pintype "bidirectional"))
      (node (ref "Q1-LS1C") (pin "2") (pinfunction "C_2") (pintype "passive"))
      (node (ref "R1-LS1C") (pin "1") (pinfunction "1_1") (pintype "passive"))
    )
    (net (code "57") (name "Net-(Q2-0C-B)") (class "Default")
      (node (ref "Q2-0C") (pin "1") (pinfunction "B_1") (pintype "passive"))
      (node (ref "R2-Q0C") (pin "1") (pinfunction "1_1") (pintype "passive"))
    )
    (net (code "58") (name "Net-(Q2-0C-C)") (class "Default")
      (node (ref "Q2-0C") (pin "2") (pinfunction "C_2") (pintype "passive"))
      (node (ref "R1-Q0C") (pin "2") (pinfunction "2_2") (pintype "passive"))
    )
    (net (code "59") (name "Net-(Q2-C-B)") (class "Default")
      (node (ref "Q2-C") (pin "1") (pinfunction "B_1") (pintype "passive"))
      (node (ref "R-Q2C") (pin "1") (pinfunction "1_1") (pintype "passive"))
    )
    (net (code "60") (name "Net-(Q2-C-C)") (class "Default")
      (node (ref "Q2-C") (pin "3") (pinfunction "C_3") (pintype "passive"))
      (node (ref "R2A-C") (pin "1") (pinfunction "1_1") (pintype "passive"))
      (node (ref "R2B-C") (pin "1") (pinfunction "1_1") (pintype "passive"))
    )
    (net (code "61") (name "Net-(Q2-C1-B)") (class "Default")
      (node (ref "Q2-C1") (pin "1") (pinfunction "B_1") (pintype "passive"))
      (node (ref "R-Q2C1") (pin "1") (pinfunction "1_1") (pintype "passive"))
    )
    (net (code "62") (name "Net-(R2-LS1C-Pad2)") (class "Default")
      (node (ref "R2-LS1C") (pin "2") (pinfunction "2_2") (pintype "passive"))
      (node (ref "VR1-LS1C") (pin "E") (pinfunction "E_E") (pintype "passive"))
    )
    (net (code "63") (name "Net-(U0-C-BOOT0)") (class "Default")
      (node (ref "R1-0C") (pin "1") (pinfunction "1_1") (pintype "passive"))
      (node (ref "U0-C") (pin "138") (pinfunction "BOOT0_138") (pintype "bidirectional"))
    )
    (net (code "64") (name "Net-(U0-C-VCAP_1)") (class "Default")
      (node (ref "C16-0C") (pin "1") (pinfunction "1_1") (pintype "passive"))
      (node (ref "U0-C") (pin "71") (pinfunction "VCAP_1_71") (pintype "bidirectional"))
    )
    (net (code "65") (name "Net-(U0-C-VCAP_2)") (class "Default")
      (node (ref "C17-0C") (pin "1") (pinfunction "1_1") (pintype "passive"))
      (node (ref "U0-C") (pin "106") (pinfunction "VCAP_2_106") (pintype "bidirectional"))
    )
    (net (code "66") (name "Net-(U2-C-ADDR)") (class "Default")
      (node (ref "R3-2C") (pin "2") (pinfunction "2_2") (pintype "passive"))
      (node (ref "U2-C") (pin "1") (pinfunction "ADDR_1") (pintype "bidirectional"))
    )
    (net (code "67") (name "OSC_IN") (class "Default")
      (node (ref "C1-Y1C") (pin "1") (pinfunction "1_1") (pintype "passive"))
      (node (ref "U0-C") (pin "23") (pinfunction "PH0_23") (pintype "bidirectional"))
      (node (ref "Y1-C") (pin "P$2") (pinfunction "2_P$2") (pintype "passive"))
    )
    (net (code "68") (name "OSC_OUT") (class "Default")
      (node (ref "C2-Y1C") (pin "1") (pinfunction "1_1") (pintype "passive"))
      (node (ref "U0-C") (pin "24") (pinfunction "PH1_24") (pintype "bidirectional"))
      (node (ref "Y1-C") (pin "P$1") (pinfunction "1_P$1") (pintype "passive"))
    )
    (net (code "69") (name "PB12") (class "Default")
      (node (ref "JA1-C") (pin "5") (pinfunction "5_5") (pintype "passive"))
      (node (ref "U0-C") (pin "73") (pinfunction "PB12_73") (pintype "bidirectional"))
    )
    (net (code "70") (name "PB13") (class "Default")
      (node (ref "JA2-C") (pin "5") (pinfunction "5_5") (pintype "passive"))
      (node (ref "U0-C") (pin "74") (pinfunction "PB13_74") (pintype "bidirectional"))
    )
    (net (code "71") (name "PB14") (class "Default")
      (node (ref "JA1-C") (pin "4") (pinfunction "4_4") (pintype "passive"))
      (node (ref "U0-C") (pin "75") (pinfunction "PB14_75") (pintype "bidirectional"))
    )
    (net (code "72") (name "PB15") (class "Default")
      (node (ref "JA2-C") (pin "4") (pinfunction "4_4") (pintype "passive"))
      (node (ref "U0-C") (pin "76") (pinfunction "PB15_76") (pintype "bidirectional"))
    )
    (net (code "73") (name "PD8") (class "Default")
      (node (ref "JA1-C") (pin "3") (pinfunction "3_3") (pintype "passive"))
      (node (ref "U0-C") (pin "77") (pinfunction "PD8_77") (pintype "bidirectional"))
    )
    (net (code "74") (name "PD9") (class "Default")
      (node (ref "JA2-C") (pin "3") (pinfunction "3_3") (pintype "passive"))
      (node (ref "U0-C") (pin "78") (pinfunction "PD9_78") (pintype "bidirectional"))
    )
    (net (code "75") (name "PD10") (class "Default")
      (node (ref "JA1-C") (pin "2") (pinfunction "2_2") (pintype "passive"))
      (node (ref "U0-C") (pin "79") (pinfunction "PD10_79") (pintype "bidirectional"))
    )
    (net (code "76") (name "PD11") (class "Default")
      (node (ref "JA2-C") (pin "2") (pinfunction "2_2") (pintype "passive"))
      (node (ref "U0-C") (pin "80") (pinfunction "PD11_80") (pintype "bidirectional"))
    )
    (net (code "77") (name "PD12") (class "Default")
      (node (ref "JA1-C") (pin "1") (pinfunction "1_1") (pintype "passive"))
      (node (ref "U0-C") (pin "81") (pinfunction "PD12_81") (pintype "bidirectional"))
    )
    (net (code "78") (name "PD13") (class "Default")
      (node (ref "JA2-C") (pin "1") (pinfunction "1_1") (pintype "passive"))
      (node (ref "U0-C") (pin "82") (pinfunction "PD13_82") (pintype "bidirectional"))
    )
    (net (code "79") (name "RTS") (class "Default")
      (node (ref "J1-CP") (pin "1") (pinfunction "1_1") (pintype "passive"))
      (node (ref "U0-C") (pin "35") (pinfunction "PA1_35") (pintype "bidirectional"))
    )
    (net (code "80") (name "SCL-1") (class "Default")
      (node (ref "R2-2C") (pin "2") (pinfunction "2_2") (pintype "passive"))
      (node (ref "U0-C") (pin "100") (pinfunction "PA8_100") (pintype "bidirectional"))
      (node (ref "U2-C") (pin "10") (pinfunction "SCL_10") (pintype "bidirectional"))
    )
    (net (code "81") (name "SDA-1") (class "Default")
      (node (ref "R1-2C") (pin "2") (pinfunction "2_2") (pintype "passive"))
      (node (ref "U0-C") (pin "99") (pinfunction "PC9_99") (pintype "bidirectional"))
      (node (ref "U2-C") (pin "9") (pinfunction "SDA_9") (pintype "bidirectional"))
    )
    (net (code "82") (name "SENSE_A") (class "Default")
      (node (ref "J3-CP") (pin "1") (pinfunction "1_1") (pintype "passive"))
      (node (ref "U0-C") (pin "18") (pinfunction "PF6_18") (pintype "bidirectional"))
      (node (ref "U2-C") (pin "4") (pinfunction "AIN0_4") (pintype "bidirectional"))
    )
    (net (code "83") (name "SENSE_B") (class "Default")
      (node (ref "J3-CP") (pin "2") (pinfunction "2_2") (pintype "passive"))
      (node (ref "U0-C") (pin "19") (pinfunction "PF7_19") (pintype "bidirectional"))
      (node (ref "U2-C") (pin "5") (pinfunction "AIN1_5") (pintype "bidirectional"))
    )
    (net (code "84") (name "SENSE_C") (class "Default")
      (node (ref "J3-CP") (pin "3") (pinfunction "3_3") (pintype "passive"))
      (node (ref "U0-C") (pin "20") (pinfunction "PF8_20") (pintype "bidirectional"))
      (node (ref "U2-C") (pin "6") (pinfunction "AIN2_6") (pintype "bidirectional"))
    )
    (net (code "85") (name "SENSE_D") (class "Default")
      (node (ref "J3-CP") (pin "4") (pinfunction "4_4") (pintype "passive"))
      (node (ref "U0-C") (pin "21") (pinfunction "PF9_21") (pintype "bidirectional"))
      (node (ref "U2-C") (pin "7") (pinfunction "AIN3_7") (pintype "bidirectional"))
    )
    (net (code "86") (name "SENSOR-ERROR") (class "Default")
      (node (ref "J3-CS") (pin "2") (pinfunction "2_2") (pintype "passive"))
      (node (ref "Q2-C1") (pin "3") (pinfunction "C_3") (pintype "passive"))
    )
    (net (code "87") (name "SENSOR-ERROR_GPIO") (class "Default")
      (node (ref "R-Q2C1") (pin "2") (pinfunction "2_2") (pintype "passive"))
      (node (ref "U0-C") (pin "64") (pinfunction "PE11_64") (pintype "bidirectional"))
    )
    (net (code "88") (name "SENSOR-NOMINAL") (class "Default")
      (node (ref "J3-CS") (pin "1") (pinfunction "1_1") (pintype "passive"))
      (node (ref "U0-C") (pin "63") (pinfunction "PE10_63") (pintype "bidirectional"))
    )
    (net (code "89") (name "STORAGE-ERROR") (class "Default")
      (node (ref "R5-C") (pin "1") (pinfunction "1_1") (pintype "passive"))
      (node (ref "U0-C") (pin "58") (pinfunction "PE7_58") (pintype "bidirectional"))
    )
    (net (code "90") (name "SWCLK") (class "Default")
      (node (ref "J1-C") (pin "2") (pinfunction "2_2") (pintype "passive"))
      (node (ref "U0-C") (pin "109") (pinfunction "PA14_109") (pintype "bidirectional"))
    )
    (net (code "91") (name "SWDIO") (class "Default")
      (node (ref "J1-C") (pin "3") (pinfunction "3_3") (pintype "passive"))
      (node (ref "U0-C") (pin "105") (pinfunction "PA13_105") (pintype "bidirectional"))
    )
    (net (code "92") (name "SWO") (class "Default")
      (node (ref "J1-C") (pin "5") (pinfunction "5_5") (pintype "passive"))
      (node (ref "U0-C") (pin "133") (pinfunction "PB3_133") (pintype "bidirectional"))
    )
    (net (code "93") (name "U1S-CHECK") (class "Default")
      (node (ref "J3-CS") (pin "3") (pinfunction "3_3") (pintype "passive"))
      (node (ref "U0-C") (pin "65") (pinfunction "PE12_65") (pintype "bidirectional"))
    )
    (net (code "94") (name "U2S-CHECK") (class "Default")
      (node (ref "J3-CS") (pin "4") (pinfunction "4_4") (pintype "passive"))
      (node (ref "U0-C") (pin "66") (pinfunction "PE13_66") (pintype "bidirectional"))
    )
    (net (code "95") (name "U2S-ST") (class "Default")
      (node (ref "J3-CS") (pin "7") (pinfunction "7_7") (pintype "passive"))
      (node (ref "U0-C") (pin "69") (pinfunction "PB10_69") (pintype "bidirectional"))
    )
    (net (code "96") (name "U3S-CHECK") (class "Default")
      (node (ref "J3-CS") (pin "5") (pinfunction "5_5") (pintype "passive"))
      (node (ref "U0-C") (pin "67") (pinfunction "PE14_67") (pintype "bidirectional"))
    )
    (net (code "97") (name "U4S-CHECK") (class "Default")
      (node (ref "J3-CS") (pin "6") (pinfunction "6_6") (pintype "passive"))
      (node (ref "U0-C") (pin "68") (pinfunction "PE15_68") (pintype "bidirectional"))
    )
    (net (code "98") (name "US2-STATUS") (class "Default")
      (node (ref "J3-CS") (pin "8") (pinfunction "8_8") (pintype "passive"))
      (node (ref "U0-C") (pin "70") (pinfunction "PB11_70") (pintype "bidirectional"))
    )
    (net (code "99") (name "VDDA") (class "Default")
      (node (ref "FB1-0C") (pin "2") (pinfunction "2_2") (pintype "bidirectional"))
      (node (ref "U0-C") (pin "32") (pinfunction "VREF+_32") (pintype "input"))
      (node (ref "U0-C") (pin "33") (pinfunction "VDDA_33") (pintype "power_in"))
    )
    (net (code "100") (name "VUSB") (class "Default")
      (node (ref "J2-C") (pin "1") (pinfunction "VBUS_1") (pintype "power_in"))
      (node (ref "JP-CP") (pin "4") (pinfunction "4_4") (pintype "passive"))
    )
    (net (code "101") (name "WP") (class "Default")
      (node (ref "U0-C") (pin "115") (pinfunction "PD1_115") (pintype "bidirectional"))
      (node (ref "U1-C") (pin "3") (pinfunction "~{WP}/IO2_3") (pintype "bidirectional"))
    )
    (net (code "102") (name "unconnected-(JP-CS-Pad4)") (class "Default")
      (node (ref "JP-CS") (pin "4") (pinfunction "4_4") (pintype "passive"))
    )
    (net (code "103") (name "unconnected-(S0-0C-P-Pad3)") (class "Default")
      (node (ref "S0-0C") (pin "3") (pinfunction "P_3") (pintype "passive"))
    )
    (net (code "104") (name "unconnected-(S0-0C-S-Pad1)") (class "Default")
      (node (ref "S0-0C") (pin "1") (pinfunction "S_1") (pintype "passive"))
    )
    (net (code "105") (name "unconnected-(S1-0C-P-Pad3)") (class "Default")
      (node (ref "S1-0C") (pin "3") (pinfunction "P_3") (pintype "passive"))
    )
    (net (code "106") (name "unconnected-(S1-0C-S1-Pad2)") (class "Default")
      (node (ref "S1-0C") (pin "2") (pinfunction "S1_2") (pintype "passive"))
    )
    (net (code "107") (name "unconnected-(U0-C-PA4-Pad40)") (class "Default")
      (node (ref "U0-C") (pin "40") (pinfunction "PA4_40") (pintype "bidirectional"))
    )
    (net (code "108") (name "unconnected-(U0-C-PA9-Pad101)") (class "Default")
      (node (ref "U0-C") (pin "101") (pinfunction "PA9_101") (pintype "bidirectional"))
    )
    (net (code "109") (name "unconnected-(U0-C-PA15-Pad110)") (class "Default")
      (node (ref "U0-C") (pin "110") (pinfunction "PA15_110") (pintype "bidirectional"))
    )
    (net (code "110") (name "unconnected-(U0-C-PB2-Pad48)") (class "Default")
      (node (ref "U0-C") (pin "48") (pinfunction "PB2_48") (pintype "bidirectional"))
    )
    (net (code "111") (name "unconnected-(U0-C-PB4-Pad134)") (class "Default")
      (node (ref "U0-C") (pin "134") (pinfunction "PB4_134") (pintype "bidirectional"))
    )
    (net (code "112") (name "unconnected-(U0-C-PB5-Pad135)") (class "Default")
      (node (ref "U0-C") (pin "135") (pinfunction "PB5_135") (pintype "bidirectional"))
    )
    (net (code "113") (name "unconnected-(U0-C-PB6-Pad136)") (class "Default")
      (node (ref "U0-C") (pin "136") (pinfunction "PB6_136") (pintype "bidirectional"))
    )
    (net (code "114") (name "unconnected-(U0-C-PB7-Pad137)") (class "Default")
      (node (ref "U0-C") (pin "137") (pinfunction "PB7_137") (pintype "bidirectional"))
    )
    (net (code "115") (name "unconnected-(U0-C-PB8-Pad139)") (class "Default")
      (node (ref "U0-C") (pin "139") (pinfunction "PB8_139") (pintype "bidirectional"))
    )
    (net (code "116") (name "unconnected-(U0-C-PB9-Pad140)") (class "Default")
      (node (ref "U0-C") (pin "140") (pinfunction "PB9_140") (pintype "bidirectional"))
    )
    (net (code "117") (name "unconnected-(U0-C-PC0-Pad26)") (class "Default")
      (node (ref "U0-C") (pin "26") (pinfunction "PC0_26") (pintype "bidirectional"))
    )
    (net (code "118") (name "unconnected-(U0-C-PC1-Pad27)") (class "Default")
      (node (ref "U0-C") (pin "27") (pinfunction "PC1_27") (pintype "bidirectional"))
    )
    (net (code "119") (name "unconnected-(U0-C-PC2-Pad28)") (class "Default")
      (node (ref "U0-C") (pin "28") (pinfunction "PC2_28") (pintype "bidirectional"))
    )
    (net (code "120") (name "unconnected-(U0-C-PC3-Pad29)") (class "Default")
      (node (ref "U0-C") (pin "29") (pinfunction "PC3_29") (pintype "bidirectional"))
    )
    (net (code "121") (name "unconnected-(U0-C-PC13-Pad7)") (class "Default")
      (node (ref "U0-C") (pin "7") (pinfunction "PC13_7") (pintype "bidirectional"))
    )
    (net (code "122") (name "unconnected-(U0-C-PC14-Pad8)") (class "Default")
      (node (ref "U0-C") (pin "8") (pinfunction "PC14_8") (pintype "bidirectional"))
    )
    (net (code "123") (name "unconnected-(U0-C-PC15-Pad9)") (class "Default")
      (node (ref "U0-C") (pin "9") (pinfunction "PC15_9") (pintype "bidirectional"))
    )
    (net (code "124") (name "unconnected-(U0-C-PD3-Pad117)") (class "Default")
      (node (ref "U0-C") (pin "117") (pinfunction "PD3_117") (pintype "bidirectional"))
    )
    (net (code "125") (name "unconnected-(U0-C-PD4-Pad118)") (class "Default")
      (node (ref "U0-C") (pin "118") (pinfunction "PD4_118") (pintype "bidirectional"))
    )
    (net (code "126") (name "unconnected-(U0-C-PD5-Pad119)") (class "Default")
      (node (ref "U0-C") (pin "119") (pinfunction "PD5_119") (pintype "bidirectional"))
    )
    (net (code "127") (name "unconnected-(U0-C-PD6-Pad122)") (class "Default")
      (node (ref "U0-C") (pin "122") (pinfunction "PD6_122") (pintype "bidirectional"))
    )
    (net (code "128") (name "unconnected-(U0-C-PD7-Pad123)") (class "Default")
      (node (ref "U0-C") (pin "123") (pinfunction "PD7_123") (pintype "bidirectional"))
    )
    (net (code "129") (name "unconnected-(U0-C-PD14-Pad85)") (class "Default")
      (node (ref "U0-C") (pin "85") (pinfunction "PD14_85") (pintype "bidirectional"))
    )
    (net (code "130") (name "unconnected-(U0-C-PD15-Pad86)") (class "Default")
      (node (ref "U0-C") (pin "86") (pinfunction "PD15_86") (pintype "bidirectional"))
    )
    (net (code "131") (name "unconnected-(U0-C-PE0-Pad141)") (class "Default")
      (node (ref "U0-C") (pin "141") (pinfunction "PE0_141") (pintype "bidirectional"))
    )
    (net (code "132") (name "unconnected-(U0-C-PE1-Pad142)") (class "Default")
      (node (ref "U0-C") (pin "142") (pinfunction "PE1_142") (pintype "bidirectional"))
    )
    (net (code "133") (name "unconnected-(U0-C-PE3-Pad2)") (class "Default")
      (node (ref "U0-C") (pin "2") (pinfunction "PE3_2") (pintype "bidirectional"))
    )
    (net (code "134") (name "unconnected-(U0-C-PE4-Pad3)") (class "Default")
      (node (ref "U0-C") (pin "3") (pinfunction "PE4_3") (pintype "bidirectional"))
    )
    (net (code "135") (name "unconnected-(U0-C-PE5-Pad4)") (class "Default")
      (node (ref "U0-C") (pin "4") (pinfunction "PE5_4") (pintype "bidirectional"))
    )
    (net (code "136") (name "unconnected-(U0-C-PE6-Pad5)") (class "Default")
      (node (ref "U0-C") (pin "5") (pinfunction "PE6_5") (pintype "bidirectional"))
    )
    (net (code "137") (name "unconnected-(U0-C-PE9-Pad60)") (class "Default")
      (node (ref "U0-C") (pin "60") (pinfunction "PE9_60") (pintype "bidirectional"))
    )
    (net (code "138") (name "unconnected-(U0-C-PF0-Pad10)") (class "Default")
      (node (ref "U0-C") (pin "10") (pinfunction "PF0_10") (pintype "bidirectional"))
    )
    (net (code "139") (name "unconnected-(U0-C-PF5-Pad15)") (class "Default")
      (node (ref "U0-C") (pin "15") (pinfunction "PF5_15") (pintype "bidirectional"))
    )
    (net (code "140") (name "unconnected-(U0-C-PF10-Pad22)") (class "Default")
      (node (ref "U0-C") (pin "22") (pinfunction "PF10_22") (pintype "bidirectional"))
    )
    (net (code "141") (name "unconnected-(U0-C-PF11-Pad49)") (class "Default")
      (node (ref "U0-C") (pin "49") (pinfunction "PF11_49") (pintype "bidirectional"))
    )
    (net (code "142") (name "unconnected-(U0-C-PF12-Pad50)") (class "Default")
      (node (ref "U0-C") (pin "50") (pinfunction "PF12_50") (pintype "bidirectional"))
    )
    (net (code "143") (name "unconnected-(U0-C-PG2-Pad87)") (class "Default")
      (node (ref "U0-C") (pin "87") (pinfunction "PG2_87") (pintype "bidirectional"))
    )
    (net (code "144") (name "unconnected-(U0-C-PG3-Pad88)") (class "Default")
      (node (ref "U0-C") (pin "88") (pinfunction "PG3_88") (pintype "bidirectional"))
    )
    (net (code "145") (name "unconnected-(U0-C-PG5-Pad90)") (class "Default")
      (node (ref "U0-C") (pin "90") (pinfunction "PG5_90") (pintype "bidirectional"))
    )
    (net (code "146") (name "unconnected-(U0-C-PG6-Pad91)") (class "Default")
      (node (ref "U0-C") (pin "91") (pinfunction "PG6_91") (pintype "bidirectional"))
    )
    (net (code "147") (name "unconnected-(U0-C-PG7-Pad92)") (class "Default")
      (node (ref "U0-C") (pin "92") (pinfunction "PG7_92") (pintype "bidirectional"))
    )
    (net (code "148") (name "unconnected-(U0-C-PG8-Pad93)") (class "Default")
      (node (ref "U0-C") (pin "93") (pinfunction "PG8_93") (pintype "bidirectional"))
    )
    (net (code "149") (name "unconnected-(U0-C-PG9-Pad124)") (class "Default")
      (node (ref "U0-C") (pin "124") (pinfunction "PG9_124") (pintype "bidirectional"))
    )
    (net (code "150") (name "unconnected-(U0-C-PG10-Pad125)") (class "Default")
      (node (ref "U0-C") (pin "125") (pinfunction "PG10_125") (pintype "bidirectional"))
    )
    (net (code "151") (name "unconnected-(U0-C-PG11-Pad126)") (class "Default")
      (node (ref "U0-C") (pin "126") (pinfunction "PG11_126") (pintype "bidirectional"))
    )
    (net (code "152") (name "unconnected-(U0-C-PG12-Pad127)") (class "Default")
      (node (ref "U0-C") (pin "127") (pinfunction "PG12_127") (pintype "bidirectional"))
    )
    (net (code "153") (name "unconnected-(U0-C-PG13-Pad128)") (class "Default")
      (node (ref "U0-C") (pin "128") (pinfunction "PG13_128") (pintype "bidirectional"))
    )
    (net (code "154") (name "unconnected-(U0-C-PG14-Pad129)") (class "Default")
      (node (ref "U0-C") (pin "129") (pinfunction "PG14_129") (pintype "bidirectional"))
    )
    (net (code "155") (name "unconnected-(U0-C-PG15-Pad132)") (class "Default")
      (node (ref "U0-C") (pin "132") (pinfunction "PG15_132") (pintype "bidirectional"))
    )
    (net (code "156") (name "unconnected-(U1-C-EP-Pad9)") (class "Default")
      (node (ref "U1-C") (pin "9") (pinfunction "EP_9") (pintype "bidirectional"))
    )
  )
)
